# master_muhsin_v1.net
KiCad netlist of a schematic drawn in EAGLE
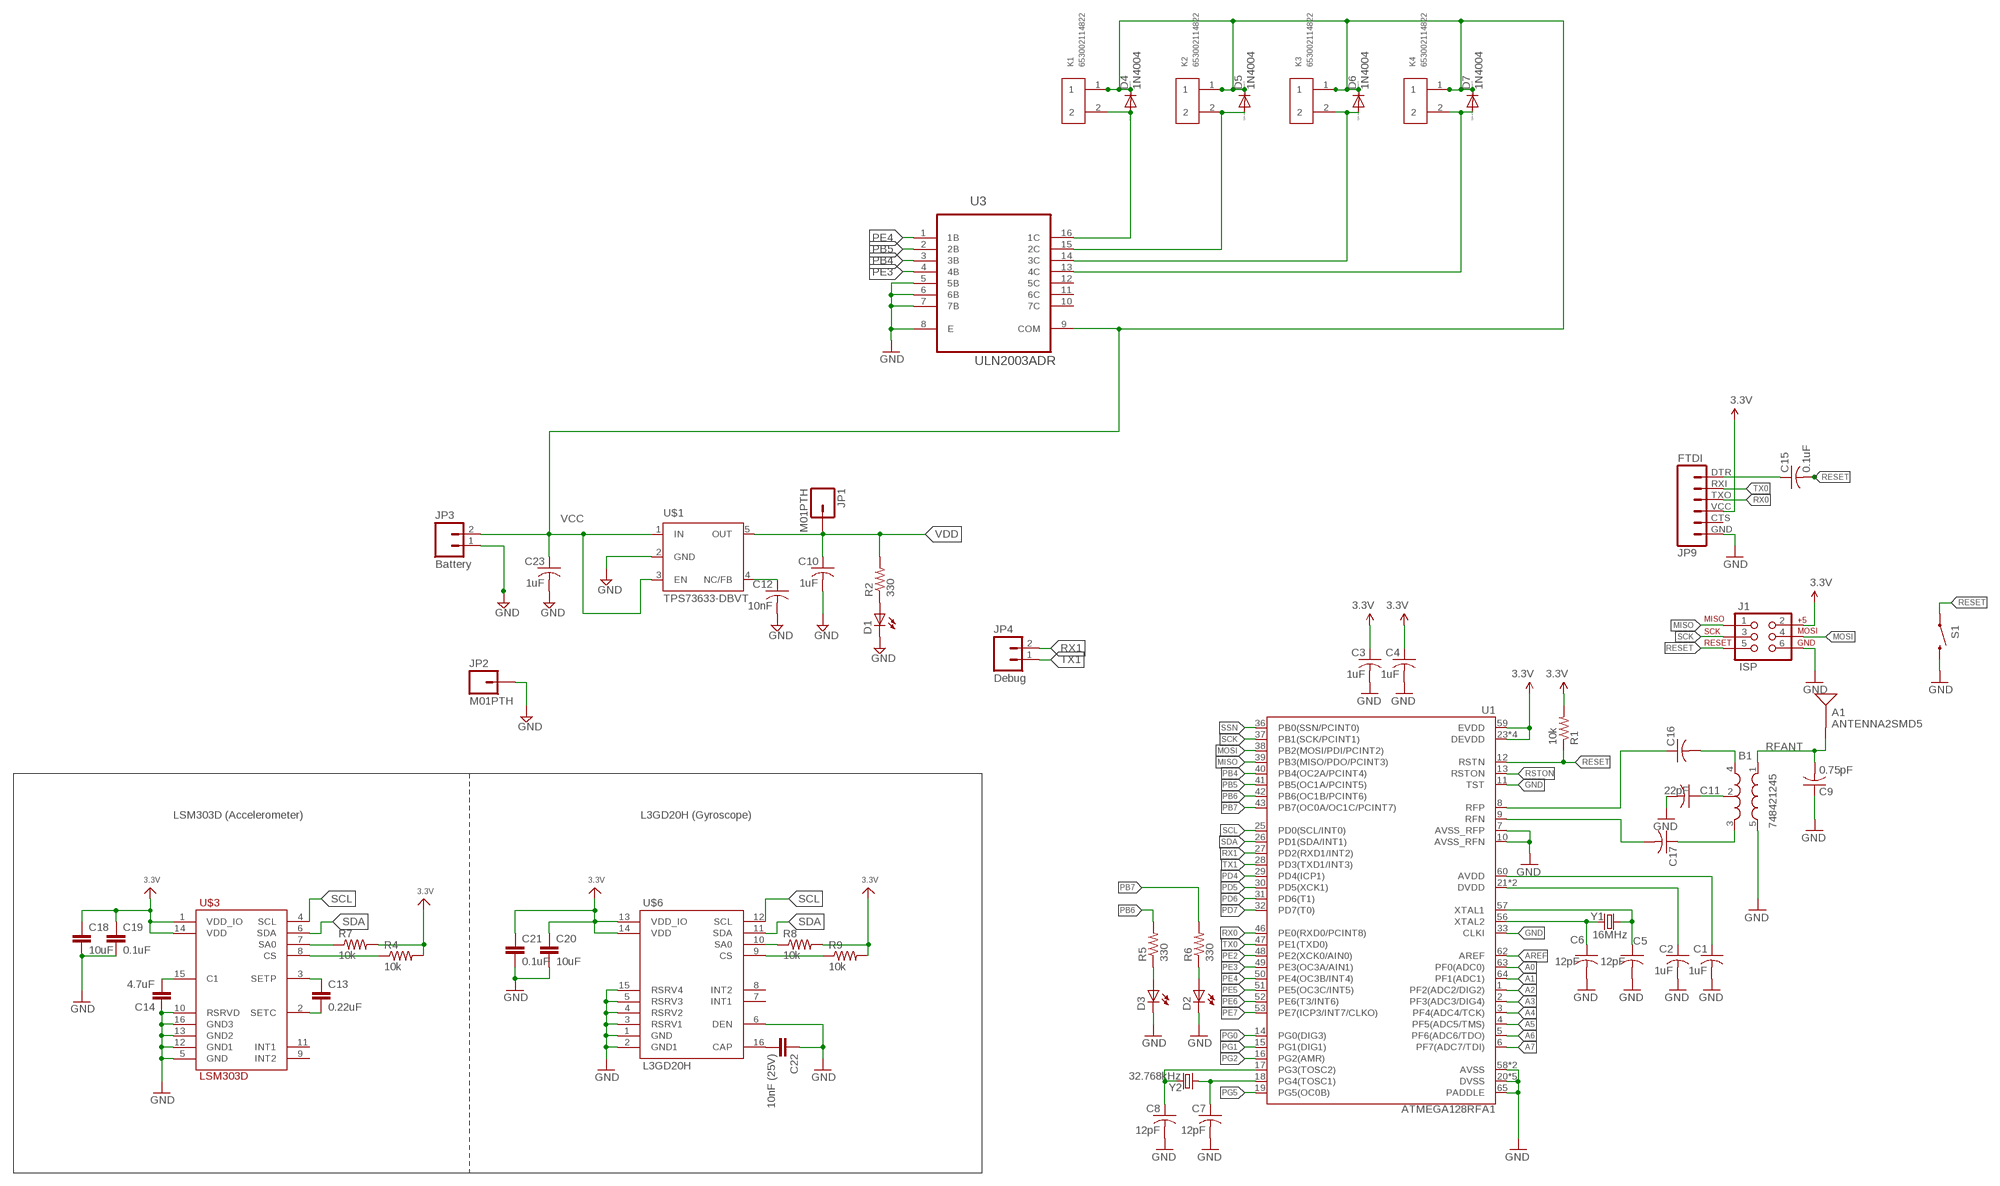
[diagram p0: schematic, sheet 1]

(export (version "E")
  (design (tool "Eeschema 10.0.6"))
  (components
    (comp (ref "A1")
      (value "ANTENNA2SMD5")
      (footprint "eagle-import:ANTENNA-CHIP5")
      (libsource (lib "eagle-import") (part "ANTENNA2SMD5"))
    )
    (comp (ref "B1")
      (value "748421245")
      (footprint "eagle-import:BALUN")
      (libsource (lib "eagle-import") (part "BALUN0805"))
    )
    (comp (ref "C1")
      (value "1uF")
      (footprint "eagle-import:C0805")
      (libsource (lib "eagle-import") (part "C-USC0805"))
    )
    (comp (ref "C2")
      (value "1uF")
      (footprint "eagle-import:C0805")
      (libsource (lib "eagle-import") (part "C-USC0805"))
    )
    (comp (ref "C3")
      (value "1uF")
      (footprint "eagle-import:C0805")
      (libsource (lib "eagle-import") (part "C-USC0805"))
    )
    (comp (ref "C4")
      (value "1uF")
      (footprint "eagle-import:C0805")
      (libsource (lib "eagle-import") (part "C-USC0805"))
    )
    (comp (ref "C5")
      (value "12pF")
      (footprint "eagle-import:C0805")
      (libsource (lib "eagle-import") (part "C-USC0805"))
    )
    (comp (ref "C6")
      (value "12pF")
      (footprint "eagle-import:C0805")
      (libsource (lib "eagle-import") (part "C-USC0805"))
    )
    (comp (ref "C7")
      (value "12pF")
      (footprint "eagle-import:C0805")
      (libsource (lib "eagle-import") (part "C-USC0805"))
    )
    (comp (ref "C8")
      (value "12pF")
      (footprint "eagle-import:C0805")
      (libsource (lib "eagle-import") (part "C-USC0805"))
    )
    (comp (ref "C9")
      (value "0.75pF")
      (footprint "eagle-import:C0805")
      (libsource (lib "eagle-import") (part "C-USC0805"))
    )
    (comp (ref "C10")
      (value "1uF")
      (footprint "eagle-import:C0805")
      (libsource (lib "eagle-import") (part "C-USC0805"))
    )
    (comp (ref "C11")
      (value "22pF")
      (footprint "eagle-import:C0805")
      (libsource (lib "eagle-import") (part "C-USC0805"))
    )
    (comp (ref "C12")
      (value "10nF")
      (footprint "eagle-import:C0805")
      (libsource (lib "eagle-import") (part "C-USC0805"))
    )
    (comp (ref "C13")
      (value "0.22uF")
      (footprint "eagle-import:0805")
      (libsource (lib "eagle-import") (part "CAP0805"))
    )
    (comp (ref "C14")
      (value "4.7uF")
      (footprint "eagle-import:0805")
      (libsource (lib "eagle-import") (part "CAP0805"))
    )
    (comp (ref "C15")
      (value "0.1uF")
      (footprint "eagle-import:C0805")
      (libsource (lib "eagle-import") (part "C-USC0805"))
    )
    (comp (ref "C16")
      (value "C-USC0805")
      (footprint "eagle-import:C0805")
      (libsource (lib "eagle-import") (part "C-USC0805"))
    )
    (comp (ref "C17")
      (value "C-USC0805")
      (footprint "eagle-import:C0805")
      (libsource (lib "eagle-import") (part "C-USC0805"))
    )
    (comp (ref "C18")
      (value "10uF")
      (footprint "eagle-import:0805")
      (libsource (lib "eagle-import") (part "CAP0805"))
    )
    (comp (ref "C19")
      (value "0.1uF")
      (footprint "eagle-import:0805")
      (libsource (lib "eagle-import") (part "CAP0805"))
    )
    (comp (ref "C20")
      (value "10uF")
      (footprint "eagle-import:0805")
      (libsource (lib "eagle-import") (part "CAP0805"))
    )
    (comp (ref "C21")
      (value "0.1uF")
      (footprint "eagle-import:0805")
      (libsource (lib "eagle-import") (part "CAP0805"))
    )
    (comp (ref "C22")
      (value "10nF (25V)")
      (footprint "eagle-import:0805")
      (libsource (lib "eagle-import") (part "CAP0805"))
    )
    (comp (ref "C23")
      (value "1uF")
      (footprint "eagle-import:C0805")
      (libsource (lib "eagle-import") (part "C-USC0805"))
    )
    (comp (ref "D1")
      (value "LED5MM")
      (footprint "eagle-import:LED5MM")
      (libsource (lib "eagle-import") (part "LED5MM"))
    )
    (comp (ref "D2")
      (value "LED5MM")
      (footprint "eagle-import:LED5MM")
      (libsource (lib "eagle-import") (part "LED5MM"))
    )
    (comp (ref "D3")
      (value "LED5MM")
      (footprint "eagle-import:LED5MM")
      (libsource (lib "eagle-import") (part "LED5MM"))
    )
    (comp (ref "D4")
      (value "1N4004")
      (footprint "eagle-import:DO41-10")
      (fields (field (name "MF") "NTE ELECTRONICS"))
      (libsource (lib "eagle-import") (part "1N4004"))
    )
    (comp (ref "D5")
      (value "1N4004")
      (footprint "eagle-import:DO41-10")
      (fields (field (name "MF") "NTE ELECTRONICS"))
      (libsource (lib "eagle-import") (part "1N4004"))
    )
    (comp (ref "D6")
      (value "1N4004")
      (footprint "eagle-import:DO41-10")
      (fields (field (name "MF") "NTE ELECTRONICS"))
      (libsource (lib "eagle-import") (part "1N4004"))
    )
    (comp (ref "D7")
      (value "1N4004")
      (footprint "eagle-import:DO41-10")
      (fields (field (name "MF") "NTE ELECTRONICS"))
      (libsource (lib "eagle-import") (part "1N4004"))
    )
    (comp (ref "J1")
      (value "ISP")
      (footprint "eagle-import:2X3-NS")
      (libsource (lib "eagle-import") (part "AVR_SPI_PRG_6NS"))
    )
    (comp (ref "JP1")
      (value "M01PTH")
      (footprint "eagle-import:1X01")
      (libsource (lib "eagle-import") (part "M01PTH"))
    )
    (comp (ref "JP2")
      (value "M01PTH")
      (footprint "eagle-import:1X01")
      (libsource (lib "eagle-import") (part "M01PTH"))
    )
    (comp (ref "JP3")
      (value "Battery")
      (footprint "eagle-import:1X02")
      (libsource (lib "eagle-import") (part "M02PTH"))
    )
    (comp (ref "JP4")
      (value "Debug")
      (footprint "eagle-import:1X02")
      (libsource (lib "eagle-import") (part "M02PTH"))
    )
    (comp (ref "JP9")
      (value "FTDI")
      (footprint "eagle-import:FTDI_BASIC")
      (libsource (lib "eagle-import") (part "FTDI_BASICPTH"))
    )
    (comp (ref "K1")
      (value "653002114822")
      (footprint "eagle-import:653002114822")
      (libsource (lib "eagle-import") (part "653002114822"))
    )
    (comp (ref "K2")
      (value "653002114822")
      (footprint "eagle-import:653002114822")
      (libsource (lib "eagle-import") (part "653002114822"))
    )
    (comp (ref "K3")
      (value "653002114822")
      (footprint "eagle-import:653002114822")
      (libsource (lib "eagle-import") (part "653002114822"))
    )
    (comp (ref "K4")
      (value "653002114822")
      (footprint "eagle-import:653002114822")
      (libsource (lib "eagle-import") (part "653002114822"))
    )
    (comp (ref "R1")
      (value "10k")
      (footprint "eagle-import:R0805")
      (libsource (lib "eagle-import") (part "R-US_R0805"))
    )
    (comp (ref "R2")
      (value "330")
      (footprint "eagle-import:R0805")
      (libsource (lib "eagle-import") (part "R-US_R0805"))
    )
    (comp (ref "R4")
      (value "10k")
      (footprint "eagle-import:0805")
      (libsource (lib "eagle-import") (part "RESISTOR0805-RES"))
    )
    (comp (ref "R5")
      (value "330")
      (footprint "eagle-import:R0805")
      (libsource (lib "eagle-import") (part "R-US_R0805"))
    )
    (comp (ref "R6")
      (value "330")
      (footprint "eagle-import:R0805")
      (libsource (lib "eagle-import") (part "R-US_R0805"))
    )
    (comp (ref "R7")
      (value "10k")
      (footprint "eagle-import:0805")
      (libsource (lib "eagle-import") (part "RESISTOR0805-RES"))
    )
    (comp (ref "R8")
      (value "10k")
      (footprint "eagle-import:0805")
      (libsource (lib "eagle-import") (part "RESISTOR0805-RES"))
    )
    (comp (ref "R9")
      (value "10k")
      (footprint "eagle-import:0805")
      (libsource (lib "eagle-import") (part "RESISTOR0805-RES"))
    )
    (comp (ref "S1")
      (value "SWITCH-MOMENTARY-2SMD")
      (footprint "eagle-import:TACTILE_SWITCH_SMD")
      (libsource (lib "eagle-import") (part "SWITCH-MOMENTARY-2SMD"))
    )
    (comp (ref "U$1")
      (value "TPS73633-DBVT")
      (footprint "eagle-import:SOT23-DBV")
      (libsource (lib "eagle-import") (part "TPS73633-DBVT"))
    )
    (comp (ref "U$3")
      (value "LSM303D")
      (footprint "eagle-import:LGA16_3X3MM")
      (libsource (lib "eagle-import") (part "LSM303D"))
    )
    (comp (ref "U$6")
      (value "L3GD20H")
      (footprint "eagle-import:LGA16_3X3MM")
      (libsource (lib "eagle-import") (part "L3GD20H"))
    )
    (comp (ref "U1")
      (value "ATMEGA128RFA1")
      (footprint "eagle-import:QFN-64")
      (libsource (lib "eagle-import") (part "ATMEGA128RFA1"))
    )
    (comp (ref "U3")
      (value "ULN2003ADR")
      (footprint "eagle-import:SOIC127P600X175-16N")
      (libsource (lib "eagle-import") (part "ULN2003ADR"))
    )
    (comp (ref "Y1")
      (value "16MHz")
      (footprint "eagle-import:CRYSTAL-SMD-5X3")
      (libsource (lib "eagle-import") (part "CRYSTAL5X3"))
    )
    (comp (ref "Y2")
      (value "32.768kHz")
      (footprint "eagle-import:CRYSTAL-32KHZ-SMD")
      (libsource (lib "eagle-import") (part "CRYSTAL32-SMD"))
    )
  )
  (nets
    (net (code "1") (name "/RFANT") (class "Default")
      (node (ref "A1") (pin "FEED") (pinfunction "SIGNAL_FEED") (pintype "bidirectional"))
      (node (ref "B1") (pin "1") (pinfunction "IN_1") (pintype "bidirectional"))
      (node (ref "C9") (pin "2") (pinfunction "2_2") (pintype "passive"))
    )
    (net (code "2") (name "/VCC") (class "Default")
      (node (ref "C23") (pin "1") (pinfunction "1_1") (pintype "passive"))
      (node (ref "D4") (pin "C") (pinfunction "C_C") (pintype "passive"))
      (node (ref "D5") (pin "C") (pinfunction "C_C") (pintype "passive"))
      (node (ref "D6") (pin "C") (pinfunction "C_C") (pintype "passive"))
      (node (ref "D7") (pin "C") (pinfunction "C_C") (pintype "passive"))
      (node (ref "JP3") (pin "2") (pinfunction "2_2") (pintype "passive"))
      (node (ref "K1") (pin "1") (pinfunction "1_1") (pintype "bidirectional"))
      (node (ref "K2") (pin "1") (pinfunction "1_1") (pintype "bidirectional"))
      (node (ref "K3") (pin "1") (pinfunction "1_1") (pintype "bidirectional"))
      (node (ref "K4") (pin "1") (pinfunction "1_1") (pintype "bidirectional"))
      (node (ref "U$1") (pin "1") (pinfunction "IN_1") (pintype "input"))
      (node (ref "U$1") (pin "3") (pinfunction "EN_3") (pintype "power_in"))
      (node (ref "U3") (pin "9") (pinfunction "COM_9") (pintype "output"))
    )
    (net (code "3") (name "3.3V") (class "Default")
      (node (ref "C18") (pin "1") (pinfunction "1_1") (pintype "passive"))
      (node (ref "C19") (pin "1") (pinfunction "1_1") (pintype "passive"))
      (node (ref "C20") (pin "1") (pinfunction "1_1") (pintype "passive"))
      (node (ref "C21") (pin "1") (pinfunction "1_1") (pintype "passive"))
      (node (ref "C3") (pin "1") (pinfunction "1_1") (pintype "passive"))
      (node (ref "C4") (pin "1") (pinfunction "1_1") (pintype "passive"))
      (node (ref "J1") (pin "2") (pinfunction "2_2") (pintype "passive"))
      (node (ref "JP9") (pin "VCC") (pinfunction "4_VCC") (pintype "passive"))
      (node (ref "R1") (pin "2") (pinfunction "2_2") (pintype "passive"))
      (node (ref "R4") (pin "2") (pinfunction "2_2") (pintype "passive"))
      (node (ref "R7") (pin "2") (pinfunction "2_2") (pintype "passive"))
      (node (ref "R8") (pin "2") (pinfunction "2_2") (pintype "passive"))
      (node (ref "R9") (pin "2") (pinfunction "2_2") (pintype "passive"))
      (node (ref "U$3") (pin "1") (pinfunction "VDD_IO_1") (pintype "bidirectional"))
      (node (ref "U$3") (pin "14") (pinfunction "VDD_14") (pintype "bidirectional"))
      (node (ref "U$6") (pin "13") (pinfunction "VDD_IO_13") (pintype "bidirectional"))
      (node (ref "U$6") (pin "14") (pinfunction "VDD_14") (pintype "bidirectional"))
      (node (ref "U1") (pin "23") (pinfunction "DEVDD_23") (pintype "bidirectional"))
      (node (ref "U1") (pin "34") (pinfunction "DEVDD_34") (pintype "bidirectional"))
      (node (ref "U1") (pin "44") (pinfunction "DEVDD_44") (pintype "bidirectional"))
      (node (ref "U1") (pin "54") (pinfunction "DEVDD_54") (pintype "bidirectional"))
      (node (ref "U1") (pin "59") (pinfunction "EVDD_59") (pintype "bidirectional"))
    )
    (net (code "4") (name "A0") (class "Default")
      (node (ref "U1") (pin "63") (pinfunction "PF0(ADC0)_63") (pintype "bidirectional"))
    )
    (net (code "5") (name "A1") (class "Default")
      (node (ref "U1") (pin "64") (pinfunction "PF1(ADC1)_64") (pintype "bidirectional"))
    )
    (net (code "6") (name "A2") (class "Default")
      (node (ref "U1") (pin "1") (pinfunction "PF2(ADC2/DIG2)_1") (pintype "bidirectional"))
    )
    (net (code "7") (name "A3") (class "Default")
      (node (ref "U1") (pin "2") (pinfunction "PF3(ADC3/DIG4)_2") (pintype "bidirectional"))
    )
    (net (code "8") (name "A4") (class "Default")
      (node (ref "U1") (pin "3") (pinfunction "PF4(ADC4/TCK)_3") (pintype "bidirectional"))
    )
    (net (code "9") (name "A5") (class "Default")
      (node (ref "U1") (pin "4") (pinfunction "PF5(ADC5/TMS)_4") (pintype "bidirectional"))
    )
    (net (code "10") (name "A6") (class "Default")
      (node (ref "U1") (pin "5") (pinfunction "PF6(ADC6/TDO)_5") (pintype "bidirectional"))
    )
    (net (code "11") (name "A7") (class "Default")
      (node (ref "U1") (pin "6") (pinfunction "PF7(ADC7/TDI)_6") (pintype "bidirectional"))
    )
    (net (code "12") (name "AREF") (class "Default")
      (node (ref "U1") (pin "62") (pinfunction "AREF_62") (pintype "bidirectional"))
    )
    (net (code "13") (name "GND") (class "Default")
      (node (ref "B1") (pin "5") (pinfunction "GND_5") (pintype "bidirectional"))
      (node (ref "C1") (pin "2") (pinfunction "2_2") (pintype "passive"))
      (node (ref "C10") (pin "2") (pinfunction "2_2") (pintype "passive"))
      (node (ref "C11") (pin "2") (pinfunction "2_2") (pintype "passive"))
      (node (ref "C12") (pin "2") (pinfunction "2_2") (pintype "passive"))
      (node (ref "C14") (pin "1") (pinfunction "1_1") (pintype "passive"))
      (node (ref "C18") (pin "2") (pinfunction "2_2") (pintype "passive"))
      (node (ref "C19") (pin "2") (pinfunction "2_2") (pintype "passive"))
      (node (ref "C2") (pin "2") (pinfunction "2_2") (pintype "passive"))
      (node (ref "C20") (pin "2") (pinfunction "2_2") (pintype "passive"))
      (node (ref "C21") (pin "2") (pinfunction "2_2") (pintype "passive"))
      (node (ref "C22") (pin "1") (pinfunction "1_1") (pintype "passive"))
      (node (ref "C23") (pin "2") (pinfunction "2_2") (pintype "passive"))
      (node (ref "C3") (pin "2") (pinfunction "2_2") (pintype "passive"))
      (node (ref "C4") (pin "2") (pinfunction "2_2") (pintype "passive"))
      (node (ref "C5") (pin "2") (pinfunction "2_2") (pintype "passive"))
      (node (ref "C6") (pin "2") (pinfunction "2_2") (pintype "passive"))
      (node (ref "C7") (pin "2") (pinfunction "2_2") (pintype "passive"))
      (node (ref "C8") (pin "2") (pinfunction "2_2") (pintype "passive"))
      (node (ref "C9") (pin "1") (pinfunction "1_1") (pintype "passive"))
      (node (ref "D1") (pin "K") (pinfunction "C_K") (pintype "passive"))
      (node (ref "D2") (pin "K") (pinfunction "C_K") (pintype "passive"))
      (node (ref "D3") (pin "K") (pinfunction "C_K") (pintype "passive"))
      (node (ref "J1") (pin "6") (pinfunction "6_6") (pintype "passive"))
      (node (ref "JP2") (pin "1") (pinfunction "1_1") (pintype "passive"))
      (node (ref "JP3") (pin "1") (pinfunction "1_1") (pintype "passive"))
      (node (ref "JP9") (pin "GND") (pinfunction "6_GND") (pintype "passive"))
      (node (ref "S1") (pin "3") (pinfunction "2_3") (pintype "passive"))
      (node (ref "U$1") (pin "2") (pinfunction "GND_2") (pintype "input"))
      (node (ref "U$3") (pin "10") (pinfunction "RSRVD_10") (pintype "bidirectional"))
      (node (ref "U$3") (pin "12") (pinfunction "GND1_12") (pintype "bidirectional"))
      (node (ref "U$3") (pin "13") (pinfunction "GND2_13") (pintype "bidirectional"))
      (node (ref "U$3") (pin "16") (pinfunction "GND3_16") (pintype "bidirectional"))
      (node (ref "U$3") (pin "5") (pinfunction "GND_5") (pintype "bidirectional"))
      (node (ref "U$6") (pin "1") (pinfunction "GND_1") (pintype "bidirectional"))
      (node (ref "U$6") (pin "15") (pinfunction "RSRV4_15") (pintype "bidirectional"))
      (node (ref "U$6") (pin "2") (pinfunction "GND1_2") (pintype "bidirectional"))
      (node (ref "U$6") (pin "3") (pinfunction "RSRV1_3") (pintype "bidirectional"))
      (node (ref "U$6") (pin "4") (pinfunction "RSRV2_4") (pintype "bidirectional"))
      (node (ref "U$6") (pin "5") (pinfunction "RSRV3_5") (pintype "bidirectional"))
      (node (ref "U$6") (pin "6") (pinfunction "DEN_6") (pintype "bidirectional"))
      (node (ref "U1") (pin "10") (pinfunction "AVSS_RFN_10") (pintype "bidirectional"))
      (node (ref "U1") (pin "11") (pinfunction "TST_11") (pintype "bidirectional"))
      (node (ref "U1") (pin "20") (pinfunction "DVSS_20") (pintype "bidirectional"))
      (node (ref "U1") (pin "24") (pinfunction "DVSS_24") (pintype "bidirectional"))
      (node (ref "U1") (pin "33") (pinfunction "CLKI_33") (pintype "bidirectional"))
      (node (ref "U1") (pin "35") (pinfunction "DVSS_35") (pintype "bidirectional"))
      (node (ref "U1") (pin "45") (pinfunction "DVSS_45") (pintype "bidirectional"))
      (node (ref "U1") (pin "55") (pinfunction "DVSS_55") (pintype "bidirectional"))
      (node (ref "U1") (pin "58") (pinfunction "AVSS_58") (pintype "bidirectional"))
      (node (ref "U1") (pin "61") (pinfunction "AVSS_61") (pintype "bidirectional"))
      (node (ref "U1") (pin "65") (pinfunction "PADDLE_65") (pintype "bidirectional"))
      (node (ref "U1") (pin "7") (pinfunction "AVSS_RFP_7") (pintype "bidirectional"))
      (node (ref "U3") (pin "5") (pinfunction "5B_5") (pintype "input"))
      (node (ref "U3") (pin "6") (pinfunction "6B_6") (pintype "input"))
      (node (ref "U3") (pin "7") (pinfunction "7B_7") (pintype "input"))
      (node (ref "U3") (pin "8") (pinfunction "E_8") (pintype "input"))
    )
    (net (code "14") (name "MISO") (class "Default")
      (node (ref "J1") (pin "1") (pinfunction "1_1") (pintype "passive"))
      (node (ref "U1") (pin "39") (pinfunction "PB3(MISO/PDO/PCINT3)_39") (pintype "bidirectional"))
    )
    (net (code "15") (name "MOSI") (class "Default")
      (node (ref "J1") (pin "4") (pinfunction "4_4") (pintype "passive"))
      (node (ref "U1") (pin "38") (pinfunction "PB2(MOSI/PDI/PCINT2)_38") (pintype "bidirectional"))
    )
    (net (code "16") (name "Net-(B1-GND-Pad2)") (class "Default")
      (node (ref "B1") (pin "2") (pinfunction "GND_2") (pintype "bidirectional"))
      (node (ref "C11") (pin "1") (pinfunction "1_1") (pintype "passive"))
    )
    (net (code "17") (name "Net-(B1-OUT1)") (class "Default")
      (node (ref "B1") (pin "4") (pinfunction "OUT1_4") (pintype "bidirectional"))
      (node (ref "C16") (pin "2") (pinfunction "2_2") (pintype "passive"))
    )
    (net (code "18") (name "Net-(B1-OUT2)") (class "Default")
      (node (ref "B1") (pin "3") (pinfunction "OUT2_3") (pintype "bidirectional"))
      (node (ref "C17") (pin "1") (pinfunction "1_1") (pintype "passive"))
    )
    (net (code "19") (name "Net-(C2-Pad1)") (class "Default")
      (node (ref "C2") (pin "1") (pinfunction "1_1") (pintype "passive"))
      (node (ref "U1") (pin "21") (pinfunction "DVDD_21") (pintype "bidirectional"))
      (node (ref "U1") (pin "22") (pinfunction "DVDD_22") (pintype "bidirectional"))
    )
    (net (code "20") (name "Net-(D1-PadA)") (class "Default")
      (node (ref "D1") (pin "A") (pinfunction "A_A") (pintype "passive"))
      (node (ref "R2") (pin "1") (pinfunction "1_1") (pintype "passive"))
    )
    (net (code "21") (name "Net-(D2-PadA)") (class "Default")
      (node (ref "D2") (pin "A") (pinfunction "A_A") (pintype "passive"))
      (node (ref "R6") (pin "1") (pinfunction "1_1") (pintype "passive"))
    )
    (net (code "22") (name "Net-(D3-PadA)") (class "Default")
      (node (ref "D3") (pin "A") (pinfunction "A_A") (pintype "passive"))
      (node (ref "R5") (pin "1") (pinfunction "1_1") (pintype "passive"))
    )
    (net (code "23") (name "Net-(JP9-1)") (class "Default")
      (node (ref "C15") (pin "1") (pinfunction "1_1") (pintype "passive"))
      (node (ref "JP9") (pin "DTR") (pinfunction "1_DTR") (pintype "passive"))
    )
    (net (code "24") (name "Net-(U$1-NC{slash}FB)") (class "Default")
      (node (ref "C12") (pin "1") (pinfunction "1_1") (pintype "passive"))
      (node (ref "U$1") (pin "4") (pinfunction "NC/FB_4") (pintype "passive"))
    )
    (net (code "25") (name "Net-(U$3-C1)") (class "Default")
      (node (ref "C14") (pin "2") (pinfunction "2_2") (pintype "passive"))
      (node (ref "U$3") (pin "15") (pinfunction "C1_15") (pintype "bidirectional"))
    )
    (net (code "26") (name "Net-(U$3-CS)") (class "Default")
      (node (ref "R4") (pin "1") (pinfunction "1_1") (pintype "passive"))
      (node (ref "U$3") (pin "8") (pinfunction "CS_8") (pintype "bidirectional"))
    )
    (net (code "27") (name "Net-(U$3-SA0)") (class "Default")
      (node (ref "R7") (pin "1") (pinfunction "1_1") (pintype "passive"))
      (node (ref "U$3") (pin "7") (pinfunction "SA0_7") (pintype "bidirectional"))
    )
    (net (code "28") (name "Net-(U$3-SETC)") (class "Default")
      (node (ref "C13") (pin "2") (pinfunction "2_2") (pintype "passive"))
      (node (ref "U$3") (pin "2") (pinfunction "SETC_2") (pintype "bidirectional"))
    )
    (net (code "29") (name "Net-(U$3-SETP)") (class "Default")
      (node (ref "C13") (pin "1") (pinfunction "1_1") (pintype "passive"))
      (node (ref "U$3") (pin "3") (pinfunction "SETP_3") (pintype "bidirectional"))
    )
    (net (code "30") (name "Net-(U$6-CAP)") (class "Default")
      (node (ref "C22") (pin "2") (pinfunction "2_2") (pintype "passive"))
      (node (ref "U$6") (pin "16") (pinfunction "CAP_16") (pintype "bidirectional"))
    )
    (net (code "31") (name "Net-(U$6-CS)") (class "Default")
      (node (ref "R9") (pin "1") (pinfunction "1_1") (pintype "passive"))
      (node (ref "U$6") (pin "9") (pinfunction "CS_9") (pintype "bidirectional"))
    )
    (net (code "32") (name "Net-(U$6-SA0)") (class "Default")
      (node (ref "R8") (pin "1") (pinfunction "1_1") (pintype "passive"))
      (node (ref "U$6") (pin "10") (pinfunction "SA0_10") (pintype "bidirectional"))
    )
    (net (code "33") (name "Net-(U1-AVDD)") (class "Default")
      (node (ref "C1") (pin "1") (pinfunction "1_1") (pintype "passive"))
      (node (ref "U1") (pin "60") (pinfunction "AVDD_60") (pintype "bidirectional"))
    )
    (net (code "34") (name "Net-(U1-PG3(TOSC2))") (class "Default")
      (node (ref "C8") (pin "1") (pinfunction "1_1") (pintype "passive"))
      (node (ref "U1") (pin "17") (pinfunction "PG3(TOSC2)_17") (pintype "bidirectional"))
      (node (ref "Y2") (pin "X2") (pinfunction "2_X2") (pintype "passive"))
    )
    (net (code "35") (name "Net-(U1-PG4(TOSC1))") (class "Default")
      (node (ref "C7") (pin "1") (pinfunction "1_1") (pintype "passive"))
      (node (ref "U1") (pin "18") (pinfunction "PG4(TOSC1)_18") (pintype "bidirectional"))
      (node (ref "Y2") (pin "X1") (pinfunction "1_X1") (pintype "passive"))
    )
    (net (code "36") (name "Net-(U1-RFN)") (class "Default")
      (node (ref "C17") (pin "2") (pinfunction "2_2") (pintype "passive"))
      (node (ref "U1") (pin "9") (pinfunction "RFN_9") (pintype "bidirectional"))
    )
    (net (code "37") (name "Net-(U1-RFP)") (class "Default")
      (node (ref "C16") (pin "1") (pinfunction "1_1") (pintype "passive"))
      (node (ref "U1") (pin "8") (pinfunction "RFP_8") (pintype "bidirectional"))
    )
    (net (code "38") (name "Net-(U1-XTAL1)") (class "Default")
      (node (ref "C5") (pin "1") (pinfunction "1_1") (pintype "passive"))
      (node (ref "U1") (pin "57") (pinfunction "XTAL1_57") (pintype "bidirectional"))
      (node (ref "Y1") (pin "3") (pinfunction "2_3") (pintype "passive"))
    )
    (net (code "39") (name "Net-(U1-XTAL2)") (class "Default")
      (node (ref "C6") (pin "1") (pinfunction "1_1") (pintype "passive"))
      (node (ref "U1") (pin "56") (pinfunction "XTAL2_56") (pintype "bidirectional"))
      (node (ref "Y1") (pin "1") (pinfunction "1_1") (pintype "passive"))
    )
    (net (code "40") (name "Net-(U3-1C)") (class "Default")
      (node (ref "D4") (pin "A") (pinfunction "A_A") (pintype "passive"))
      (node (ref "K1") (pin "2") (pinfunction "2_2") (pintype "bidirectional"))
      (node (ref "U3") (pin "16") (pinfunction "1C_16") (pintype "output"))
    )
    (net (code "41") (name "Net-(U3-2C)") (class "Default")
      (node (ref "D5") (pin "A") (pinfunction "A_A") (pintype "passive"))
      (node (ref "K2") (pin "2") (pinfunction "2_2") (pintype "bidirectional"))
      (node (ref "U3") (pin "15") (pinfunction "2C_15") (pintype "output"))
    )
    (net (code "42") (name "Net-(U3-3C)") (class "Default")
      (node (ref "D6") (pin "A") (pinfunction "A_A") (pintype "passive"))
      (node (ref "K3") (pin "2") (pinfunction "2_2") (pintype "bidirectional"))
      (node (ref "U3") (pin "14") (pinfunction "3C_14") (pintype "output"))
    )
    (net (code "43") (name "Net-(U3-4C)") (class "Default")
      (node (ref "D7") (pin "A") (pinfunction "A_A") (pintype "passive"))
      (node (ref "K4") (pin "2") (pinfunction "2_2") (pintype "bidirectional"))
      (node (ref "U3") (pin "13") (pinfunction "4C_13") (pintype "output"))
    )
    (net (code "44") (name "PB4") (class "Default")
      (node (ref "U1") (pin "40") (pinfunction "PB4(OC2A/PCINT4)_40") (pintype "bidirectional"))
      (node (ref "U3") (pin "3") (pinfunction "3B_3") (pintype "input"))
    )
    (net (code "45") (name "PB5") (class "Default")
      (node (ref "U1") (pin "41") (pinfunction "PB5(OC1A/PCINT5)_41") (pintype "bidirectional"))
      (node (ref "U3") (pin "2") (pinfunction "2B_2") (pintype "input"))
    )
    (net (code "46") (name "PB6") (class "Default")
      (node (ref "R5") (pin "2") (pinfunction "2_2") (pintype "passive"))
      (node (ref "U1") (pin "42") (pinfunction "PB6(OC1B/PCINT6)_42") (pintype "bidirectional"))
    )
    (net (code "47") (name "PB7") (class "Default")
      (node (ref "R6") (pin "2") (pinfunction "2_2") (pintype "passive"))
      (node (ref "U1") (pin "43") (pinfunction "PB7(OC0A/OC1C/PCINT7)_43") (pintype "bidirectional"))
    )
    (net (code "48") (name "PD4") (class "Default")
      (node (ref "U1") (pin "29") (pinfunction "PD4(ICP1)_29") (pintype "bidirectional"))
    )
    (net (code "49") (name "PD5") (class "Default")
      (node (ref "U1") (pin "30") (pinfunction "PD5(XCK1)_30") (pintype "bidirectional"))
    )
    (net (code "50") (name "PD6") (class "Default")
      (node (ref "U1") (pin "31") (pinfunction "PD6(T1)_31") (pintype "bidirectional"))
    )
    (net (code "51") (name "PD7") (class "Default")
      (node (ref "U1") (pin "32") (pinfunction "PD7(T0)_32") (pintype "bidirectional"))
    )
    (net (code "52") (name "PE2") (class "Default")
      (node (ref "U1") (pin "48") (pinfunction "PE2(XCK0/AIN0)_48") (pintype "bidirectional"))
    )
    (net (code "53") (name "PE3") (class "Default")
      (node (ref "U1") (pin "49") (pinfunction "PE3(OC3A/AIN1)_49") (pintype "bidirectional"))
      (node (ref "U3") (pin "4") (pinfunction "4B_4") (pintype "input"))
    )
    (net (code "54") (name "PE4") (class "Default")
      (node (ref "U1") (pin "50") (pinfunction "PE4(OC3B/INT4)_50") (pintype "bidirectional"))
      (node (ref "U3") (pin "1") (pinfunction "1B_1") (pintype "input"))
    )
    (net (code "55") (name "PE5") (class "Default")
      (node (ref "U1") (pin "51") (pinfunction "PE5(OC3C/INT5)_51") (pintype "bidirectional"))
    )
    (net (code "56") (name "PE6") (class "Default")
      (node (ref "U1") (pin "52") (pinfunction "PE6(T3/INT6)_52") (pintype "bidirectional"))
    )
    (net (code "57") (name "PE7") (class "Default")
      (node (ref "U1") (pin "53") (pinfunction "PE7(ICP3/INT7/CLKO)_53") (pintype "bidirectional"))
    )
    (net (code "58") (name "PG0") (class "Default")
      (node (ref "U1") (pin "14") (pinfunction "PG0(DIG3)_14") (pintype "bidirectional"))
    )
    (net (code "59") (name "PG1") (class "Default")
      (node (ref "U1") (pin "15") (pinfunction "PG1(DIG1)_15") (pintype "bidirectional"))
    )
    (net (code "60") (name "PG2") (class "Default")
      (node (ref "U1") (pin "16") (pinfunction "PG2(AMR)_16") (pintype "bidirectional"))
    )
    (net (code "61") (name "PG5") (class "Default")
      (node (ref "U1") (pin "19") (pinfunction "PG5(OC0B)_19") (pintype "bidirectional"))
    )
    (net (code "62") (name "RESET") (class "Default")
      (node (ref "C15") (pin "2") (pinfunction "2_2") (pintype "passive"))
      (node (ref "J1") (pin "5") (pinfunction "5_5") (pintype "passive"))
      (node (ref "R1") (pin "1") (pinfunction "1_1") (pintype "passive"))
      (node (ref "S1") (pin "1") (pinfunction "1_1") (pintype "passive"))
      (node (ref "U1") (pin "12") (pinfunction "RSTN_12") (pintype "bidirectional"))
    )
    (net (code "63") (name "RSTON") (class "Default")
      (node (ref "U1") (pin "13") (pinfunction "RSTON_13") (pintype "bidirectional"))
    )
    (net (code "64") (name "RX0") (class "Default")
      (node (ref "JP9") (pin "TXO") (pinfunction "3_TXO") (pintype "passive"))
      (node (ref "U1") (pin "46") (pinfunction "PE0(RXD0/PCINT8)_46") (pintype "bidirectional"))
    )
    (net (code "65") (name "RX1") (class "Default")
      (node (ref "JP4") (pin "2") (pinfunction "2_2") (pintype "passive"))
      (node (ref "U1") (pin "27") (pinfunction "PD2(RXD1/INT2)_27") (pintype "bidirectional"))
    )
    (net (code "66") (name "SCK") (class "Default")
      (node (ref "J1") (pin "3") (pinfunction "3_3") (pintype "passive"))
      (node (ref "U1") (pin "37") (pinfunction "PB1(SCK/PCINT1)_37") (pintype "bidirectional"))
    )
    (net (code "67") (name "SCL") (class "Default")
      (node (ref "U$3") (pin "4") (pinfunction "SCL_4") (pintype "bidirectional"))
      (node (ref "U$6") (pin "12") (pinfunction "SCL_12") (pintype "bidirectional"))
      (node (ref "U1") (pin "25") (pinfunction "PD0(SCL/INT0)_25") (pintype "bidirectional"))
    )
    (net (code "68") (name "SDA") (class "Default")
      (node (ref "U$3") (pin "6") (pinfunction "SDA_6") (pintype "bidirectional"))
      (node (ref "U$6") (pin "11") (pinfunction "SDA_11") (pintype "bidirectional"))
      (node (ref "U1") (pin "26") (pinfunction "PD1(SDA/INT1)_26") (pintype "bidirectional"))
    )
    (net (code "69") (name "SSN") (class "Default")
      (node (ref "U1") (pin "36") (pinfunction "PB0(SSN/PCINT0)_36") (pintype "bidirectional"))
    )
    (net (code "70") (name "TX0") (class "Default")
      (node (ref "JP9") (pin "RXI") (pinfunction "2_RXI") (pintype "passive"))
      (node (ref "U1") (pin "47") (pinfunction "PE1(TXD0)_47") (pintype "bidirectional"))
    )
    (net (code "71") (name "TX1") (class "Default")
      (node (ref "JP4") (pin "1") (pinfunction "1_1") (pintype "passive"))
      (node (ref "U1") (pin "28") (pinfunction "PD3(TXD1/INT3)_28") (pintype "bidirectional"))
    )
    (net (code "72") (name "VDD") (class "Default")
      (node (ref "C10") (pin "1") (pinfunction "1_1") (pintype "passive"))
      (node (ref "JP1") (pin "1") (pinfunction "1_1") (pintype "passive"))
      (node (ref "R2") (pin "2") (pinfunction "2_2") (pintype "passive"))
      (node (ref "U$1") (pin "5") (pinfunction "OUT_5") (pintype "passive"))
    )
    (net (code "73") (name "unconnected-(JP9-5-PadCTS)") (class "Default")
      (node (ref "JP9") (pin "CTS") (pinfunction "5_CTS") (pintype "passive"))
    )
    (net (code "74") (name "unconnected-(U$3-INT1-Pad11)") (class "Default")
      (node (ref "U$3") (pin "11") (pinfunction "INT1_11") (pintype "bidirectional"))
    )
    (net (code "75") (name "unconnected-(U$3-INT2-Pad9)") (class "Default")
      (node (ref "U$3") (pin "9") (pinfunction "INT2_9") (pintype "bidirectional"))
    )
    (net (code "76") (name "unconnected-(U$6-INT1-Pad7)") (class "Default")
      (node (ref "U$6") (pin "7") (pinfunction "INT1_7") (pintype "bidirectional"))
    )
    (net (code "77") (name "unconnected-(U$6-INT2-Pad8)") (class "Default")
      (node (ref "U$6") (pin "8") (pinfunction "INT2_8") (pintype "bidirectional"))
    )
    (net (code "78") (name "unconnected-(U3-5C-Pad12)") (class "Default")
      (node (ref "U3") (pin "12") (pinfunction "5C_12") (pintype "output"))
    )
    (net (code "79") (name "unconnected-(U3-6C-Pad11)") (class "Default")
      (node (ref "U3") (pin "11") (pinfunction "6C_11") (pintype "output"))
    )
    (net (code "80") (name "unconnected-(U3-7C-Pad10)") (class "Default")
      (node (ref "U3") (pin "10") (pinfunction "7C_10") (pintype "output"))
    )
  )
)
